# MCU.net
KiCad netlist of a schematic drawn in Altium Designer
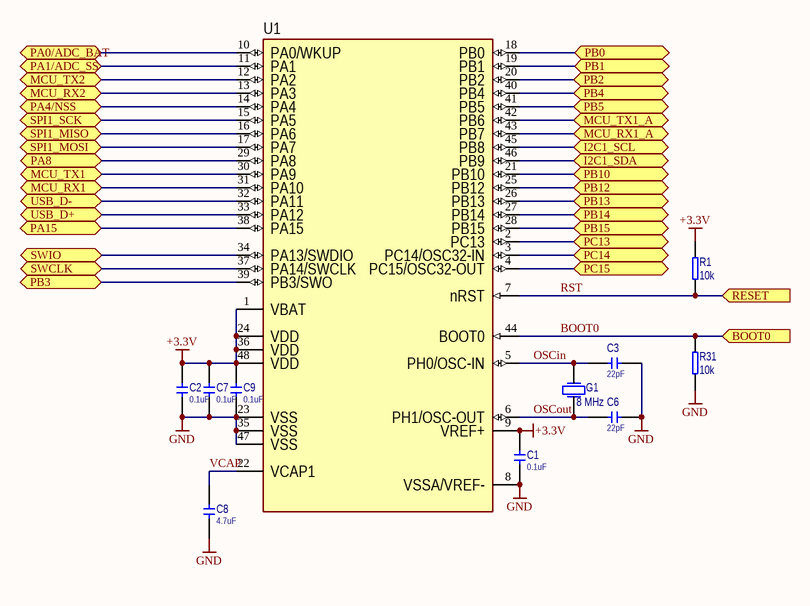
[diagram p0: MCU.SchDoc]

(export (version "E")
  (design (tool "Eeschema 10.0.6"))
  (components
    (comp (ref "C1")
      (value "0.1uF")
      (footprint "CERCAP 0402")
      (description "Capacitor")
      (fields (field (name "Comment") "CERCAP 0402 0.1uF * X7R"))
      (libsource (lib "!main") (part "!Capacitor"))
    )
    (comp (ref "C2")
      (value "0.1uF")
      (footprint "CERCAP 0402")
      (description "Capacitor")
      (fields (field (name "Comment") "CERCAP 0402 0.1uF * X7R"))
      (libsource (lib "!main") (part "!Capacitor"))
    )
    (comp (ref "C3")
      (value "22pF")
      (footprint "CERCAP 0402")
      (description "Capacitor")
      (fields (field (name "Comment") "CERCAP 0402 22pF * X7R"))
      (libsource (lib "!main") (part "!Capacitor"))
    )
    (comp (ref "C6")
      (value "22pF")
      (footprint "CERCAP 0402")
      (description "Capacitor")
      (fields (field (name "Comment") "CERCAP 0402 22pF * X7R"))
      (libsource (lib "!main") (part "!Capacitor"))
    )
    (comp (ref "C7")
      (value "0.1uF")
      (footprint "CERCAP 0402")
      (description "Capacitor")
      (fields (field (name "Comment") "CERCAP 0402 0.1uF * X7R"))
      (libsource (lib "!main") (part "!Capacitor"))
    )
    (comp (ref "C8")
      (value "4.7uF")
      (footprint "CERCAP 0603")
      (description "Capacitor")
      (fields (field (name "Comment") "CERCAP 0603 4.7uF * X7R"))
      (libsource (lib "!main") (part "!Capacitor"))
    )
    (comp (ref "C9")
      (value "0.1uF")
      (footprint "CERCAP 0402")
      (description "Capacitor")
      (fields (field (name "Comment") "CERCAP 0402 0.1uF * X7R"))
      (libsource (lib "!main") (part "!Capacitor"))
    )
    (comp (ref "G1")
      (value "8 MHz")
      (footprint "3225")
      (description "Crystal")
      (fields (field (name "Comment") "32258 MHz"))
      (libsource (lib "!main") (part "Crystal"))
    )
    (comp (ref "R1")
      (value "10k")
      (footprint "RES 0402")
      (description "Resistor")
      (fields (field (name "Comment") "RES 0402 10k"))
      (libsource (lib "!main") (part "!Resistor"))
    )
    (comp (ref "R31")
      (value "10k")
      (footprint "RES 0402")
      (description "Resistor")
      (fields (field (name "Comment") "RES 0402 10k"))
      (libsource (lib "!main") (part "!Resistor"))
    )
    (comp (ref "U1")
      (value "STM32F401CCU6")
      (footprint "QFN-48")
      (description "Cortex-M4")
      (libsource (lib "MCU_CPU") (part "STM32F401CCU6"))
    )
  )
  (nets
    (net (code "1") (name "+3.3V") (class "Default")
      (node (ref "C1") (pin "2") (pintype "passive"))
      (node (ref "C2") (pin "2") (pintype "passive"))
      (node (ref "C7") (pin "2") (pintype "passive"))
      (node (ref "C9") (pin "2") (pintype "passive"))
      (node (ref "R1") (pin "2") (pinfunction "12_2") (pintype "passive"))
      (node (ref "U1") (pin "1") (pinfunction "VBAT_1") (pintype "passive"))
      (node (ref "U1") (pin "24") (pinfunction "VDD_24") (pintype "passive"))
      (node (ref "U1") (pin "36") (pinfunction "VDD_36") (pintype "passive"))
      (node (ref "U1") (pin "48") (pinfunction "VDD_48") (pintype "passive"))
      (node (ref "U1") (pin "9") (pinfunction "VREF+_9") (pintype "passive"))
    )
    (net (code "2") (name "/BOOT0") (class "Default")
      (node (ref "R31") (pin "1") (pinfunction "11_1") (pintype "passive"))
      (node (ref "U1") (pin "44") (pinfunction "BOOT0_44") (pintype "input"))
    )
    (net (code "3") (name "/I2C1_SCL") (class "Default")
      (node (ref "U1") (pin "45") (pinfunction "PB8_45") (pintype "bidirectional"))
    )
    (net (code "4") (name "/I2C1_SDA") (class "Default")
      (node (ref "U1") (pin "46") (pinfunction "PB9_46") (pintype "bidirectional"))
    )
    (net (code "5") (name "/MCU_RX1") (class "Default")
      (node (ref "U1") (pin "31") (pinfunction "PA10_31") (pintype "bidirectional"))
    )
    (net (code "6") (name "/MCU_RX1_A") (class "Default")
      (node (ref "U1") (pin "43") (pinfunction "PB7_43") (pintype "bidirectional"))
    )
    (net (code "7") (name "/MCU_RX2") (class "Default")
      (node (ref "U1") (pin "13") (pinfunction "PA3_13") (pintype "bidirectional"))
    )
    (net (code "8") (name "/MCU_TX1") (class "Default")
      (node (ref "U1") (pin "30") (pinfunction "PA9_30") (pintype "bidirectional"))
    )
    (net (code "9") (name "/MCU_TX1_A") (class "Default")
      (node (ref "U1") (pin "42") (pinfunction "PB6_42") (pintype "bidirectional"))
    )
    (net (code "10") (name "/MCU_TX2") (class "Default")
      (node (ref "U1") (pin "12") (pinfunction "PA2_12") (pintype "bidirectional"))
    )
    (net (code "11") (name "/OSCin") (class "Default")
      (node (ref "C3") (pin "2") (pintype "passive"))
      (node (ref "G1") (pin "2") (pintype "passive"))
      (node (ref "U1") (pin "5") (pinfunction "PH0/OSC-IN_5") (pintype "bidirectional"))
    )
    (net (code "12") (name "/OSCout") (class "Default")
      (node (ref "C6") (pin "2") (pintype "passive"))
      (node (ref "G1") (pin "1") (pintype "passive"))
      (node (ref "U1") (pin "6") (pinfunction "PH1/OSC-OUT_6") (pintype "bidirectional"))
    )
    (net (code "13") (name "/PA0{slash}ADC_BAT") (class "Default")
      (node (ref "U1") (pin "10") (pinfunction "PA0/WKUP_10") (pintype "bidirectional"))
    )
    (net (code "14") (name "/PA1{slash}ADC_SS") (class "Default")
      (node (ref "U1") (pin "11") (pinfunction "PA1_11") (pintype "bidirectional"))
    )
    (net (code "15") (name "/PA4{slash}NSS") (class "Default")
      (node (ref "U1") (pin "14") (pinfunction "PA4_14") (pintype "bidirectional"))
    )
    (net (code "16") (name "/PA8") (class "Default")
      (node (ref "U1") (pin "29") (pinfunction "PA8_29") (pintype "bidirectional"))
    )
    (net (code "17") (name "/PA15") (class "Default")
      (node (ref "U1") (pin "38") (pinfunction "PA15_38") (pintype "bidirectional"))
    )
    (net (code "18") (name "/PB0") (class "Default")
      (node (ref "U1") (pin "18") (pinfunction "PB0_18") (pintype "bidirectional"))
    )
    (net (code "19") (name "/PB1") (class "Default")
      (node (ref "U1") (pin "19") (pinfunction "PB1_19") (pintype "bidirectional"))
    )
    (net (code "20") (name "/PB2") (class "Default")
      (node (ref "U1") (pin "20") (pinfunction "PB2_20") (pintype "bidirectional"))
    )
    (net (code "21") (name "/PB3") (class "Default")
      (node (ref "U1") (pin "39") (pinfunction "PB3/SWO_39") (pintype "bidirectional"))
    )
    (net (code "22") (name "/PB4") (class "Default")
      (node (ref "U1") (pin "40") (pinfunction "PB4_40") (pintype "bidirectional"))
    )
    (net (code "23") (name "/PB5") (class "Default")
      (node (ref "U1") (pin "41") (pinfunction "PB5_41") (pintype "bidirectional"))
    )
    (net (code "24") (name "/PB10") (class "Default")
      (node (ref "U1") (pin "21") (pinfunction "PB10_21") (pintype "bidirectional"))
    )
    (net (code "25") (name "/PB12") (class "Default")
      (node (ref "U1") (pin "25") (pinfunction "PB12_25") (pintype "bidirectional"))
    )
    (net (code "26") (name "/PB13") (class "Default")
      (node (ref "U1") (pin "26") (pinfunction "PB13_26") (pintype "bidirectional"))
    )
    (net (code "27") (name "/PB14") (class "Default")
      (node (ref "U1") (pin "27") (pinfunction "PB14_27") (pintype "bidirectional"))
    )
    (net (code "28") (name "/PB15") (class "Default")
      (node (ref "U1") (pin "28") (pinfunction "PB15_28") (pintype "bidirectional"))
    )
    (net (code "29") (name "/PC13") (class "Default")
      (node (ref "U1") (pin "2") (pinfunction "PC13_2") (pintype "bidirectional"))
    )
    (net (code "30") (name "/PC14") (class "Default")
      (node (ref "U1") (pin "3") (pinfunction "PC14/OSC32-IN_3") (pintype "bidirectional"))
    )
    (net (code "31") (name "/PC15") (class "Default")
      (node (ref "U1") (pin "4") (pinfunction "PC15/OSC32-OUT_4") (pintype "bidirectional"))
    )
    (net (code "32") (name "/RST") (class "Default")
      (node (ref "R1") (pin "1") (pinfunction "11_1") (pintype "passive"))
      (node (ref "U1") (pin "7") (pinfunction "nRST_7") (pintype "input"))
    )
    (net (code "33") (name "/SPI1_MISO") (class "Default")
      (node (ref "U1") (pin "16") (pinfunction "PA6_16") (pintype "bidirectional"))
    )
    (net (code "34") (name "/SPI1_MOSI") (class "Default")
      (node (ref "U1") (pin "17") (pinfunction "PA7_17") (pintype "bidirectional"))
    )
    (net (code "35") (name "/SPI1_SCK") (class "Default")
      (node (ref "U1") (pin "15") (pinfunction "PA5_15") (pintype "bidirectional"))
    )
    (net (code "36") (name "/SWCLK") (class "Default")
      (node (ref "U1") (pin "37") (pinfunction "PA14/SWCLK_37") (pintype "bidirectional"))
    )
    (net (code "37") (name "/SWIO") (class "Default")
      (node (ref "U1") (pin "34") (pinfunction "PA13/SWDIO_34") (pintype "bidirectional"))
    )
    (net (code "38") (name "/USB_D+") (class "Default")
      (node (ref "U1") (pin "33") (pinfunction "PA12_33") (pintype "bidirectional"))
    )
    (net (code "39") (name "/USB_D-") (class "Default")
      (node (ref "U1") (pin "32") (pinfunction "PA11_32") (pintype "bidirectional"))
    )
    (net (code "40") (name "/VCAP") (class "Default")
      (node (ref "C8") (pin "2") (pintype "passive"))
      (node (ref "U1") (pin "22") (pinfunction "VCAP1_22") (pintype "passive"))
    )
    (net (code "41") (name "GND") (class "Default")
      (node (ref "C1") (pin "1") (pintype "passive"))
      (node (ref "C2") (pin "1") (pintype "passive"))
      (node (ref "C3") (pin "1") (pintype "passive"))
      (node (ref "C6") (pin "1") (pintype "passive"))
      (node (ref "C7") (pin "1") (pintype "passive"))
      (node (ref "C8") (pin "1") (pintype "passive"))
      (node (ref "C9") (pin "1") (pintype "passive"))
      (node (ref "R31") (pin "2") (pinfunction "12_2") (pintype "passive"))
      (node (ref "U1") (pin "23") (pinfunction "VSS_23") (pintype "passive"))
      (node (ref "U1") (pin "35") (pinfunction "VSS_35") (pintype "passive"))
      (node (ref "U1") (pin "47") (pinfunction "VSS_47") (pintype "passive"))
      (node (ref "U1") (pin "8") (pinfunction "VSSA/VREF-_8") (pintype "passive"))
    )
  )
)
